# Gvove_-_Piezo_Vibration_Sensor_v1_1.net
KiCad netlist of a schematic drawn in EAGLE
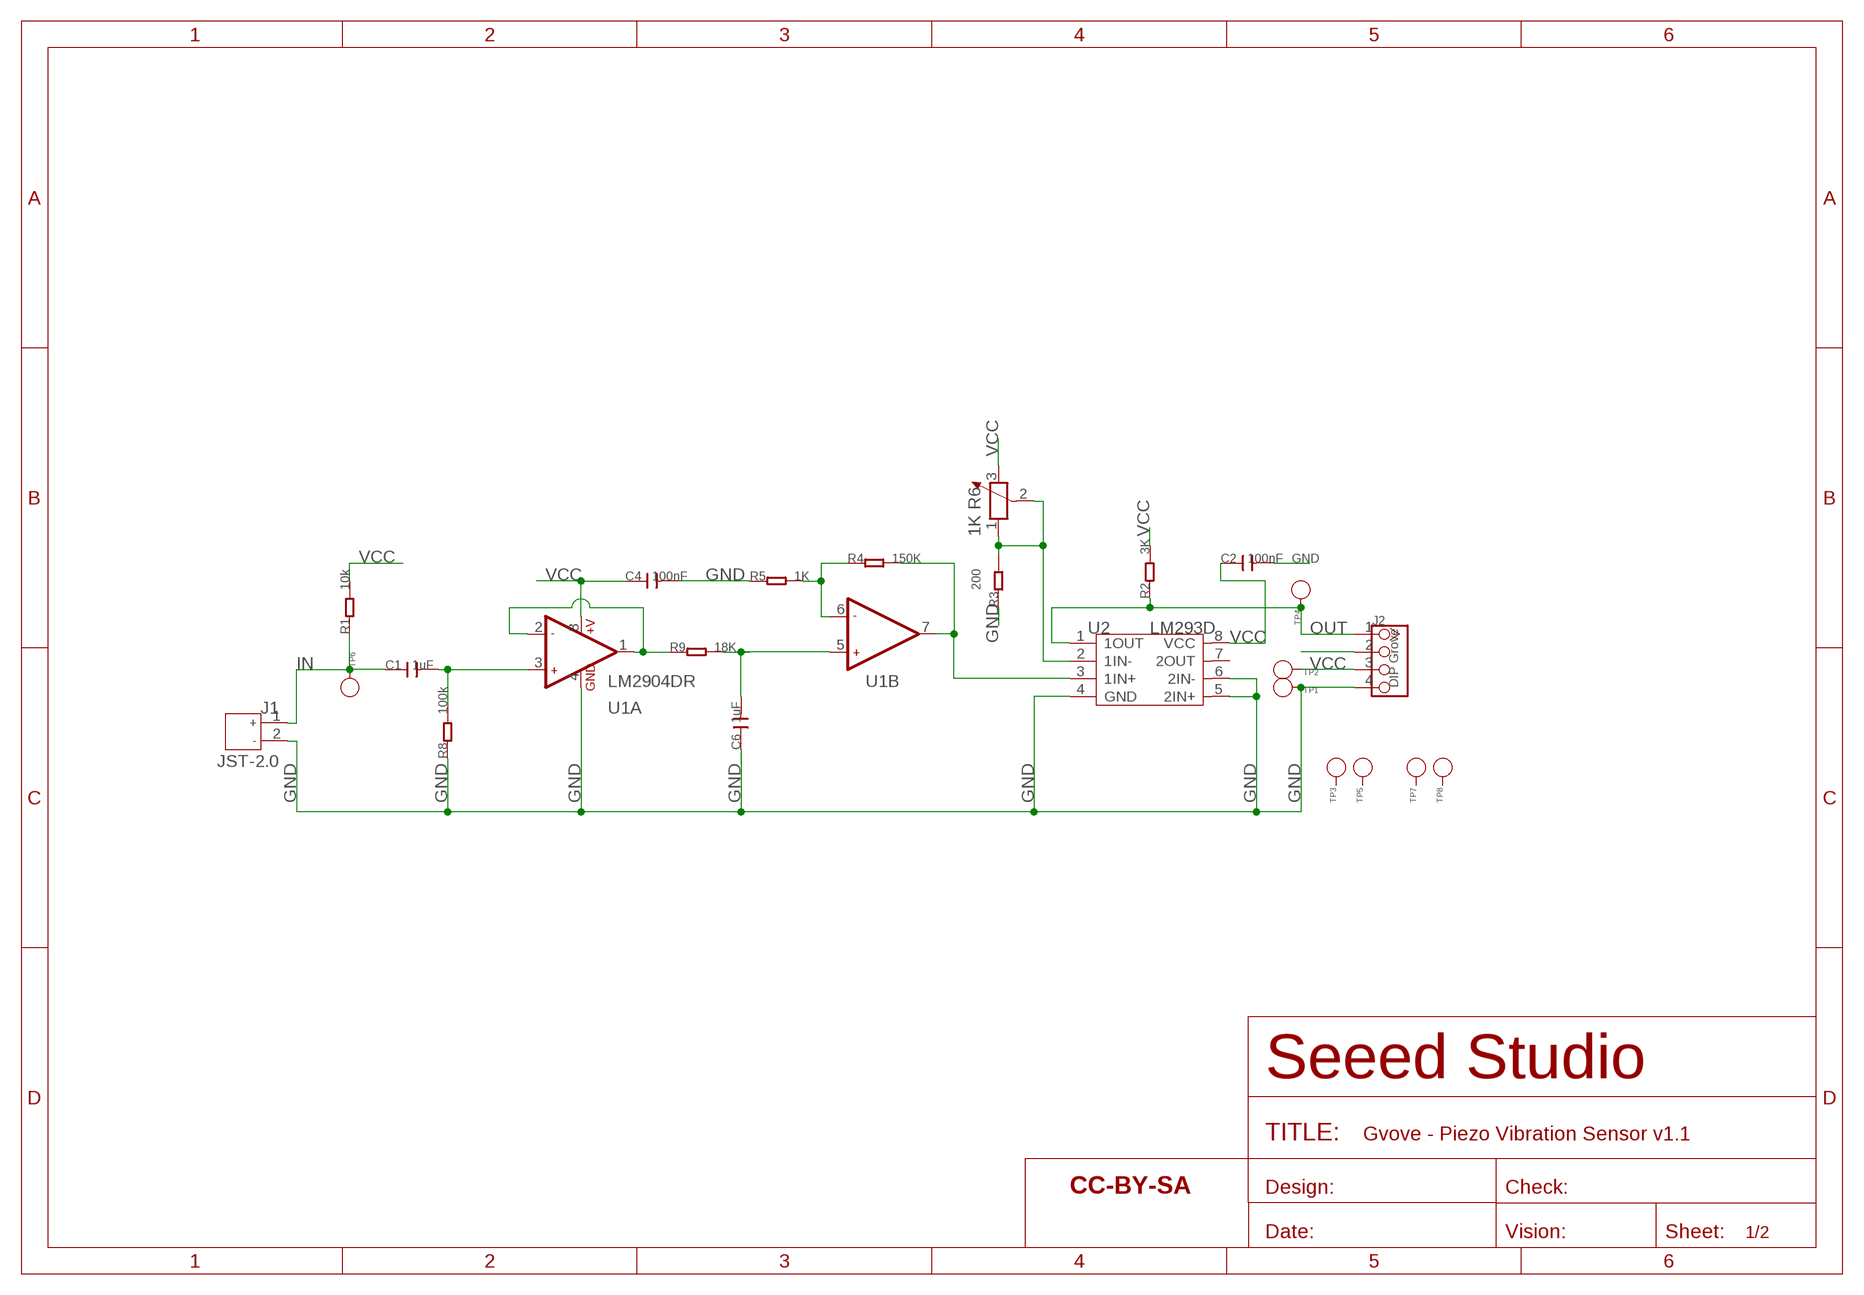
[diagram p0: schematic, sheet 1]
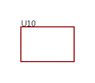
[diagram p1: schematic, sheet 2]

(export (version "E")
  (design (tool "Eeschema 10.0.6"))
  (components
    (comp (ref "U10")
      (value "TWIG'2U'")
      (footprint "eagle-import:GROVE-TEST-PLATFORM")
      (libsource (lib "eagle-import") (part "TWIG'2U'"))
    )
    (comp (ref "C1")
      (value "1uF")
      (footprint "eagle-import:C0603")
      (libsource (lib "eagle-import") (part "C-0603"))
    )
    (comp (ref "C2")
      (value "100nF")
      (footprint "eagle-import:C0603")
      (libsource (lib "eagle-import") (part "C-0603"))
    )
    (comp (ref "C4")
      (value "100nF")
      (footprint "eagle-import:C0603")
      (libsource (lib "eagle-import") (part "C-0603"))
    )
    (comp (ref "C6")
      (value "1uF")
      (footprint "eagle-import:C0603")
      (libsource (lib "eagle-import") (part "C-0603"))
    )
    (comp (ref "J1")
      (value "JST-2.0")
      (footprint "eagle-import:JST-2.0")
      (libsource (lib "eagle-import") (part "JACK-JST-2P-PW'2.0'"))
    )
    (comp (ref "J2")
      (value "DIP Grove")
      (footprint "eagle-import:4P-2.0")
      (libsource (lib "eagle-import") (part "TWIG-4P-2.0-2.0"))
    )
    (comp (ref "R1")
      (value "10k")
      (footprint "eagle-import:R0603")
      (libsource (lib "eagle-import") (part "R-0603"))
    )
    (comp (ref "R2")
      (value "3K")
      (footprint "eagle-import:R0603")
      (libsource (lib "eagle-import") (part "R-0603"))
    )
    (comp (ref "R3")
      (value "200")
      (footprint "eagle-import:R0603")
      (libsource (lib "eagle-import") (part "R-0603"))
    )
    (comp (ref "R4")
      (value "150K")
      (footprint "eagle-import:R0603")
      (libsource (lib "eagle-import") (part "R-0603"))
    )
    (comp (ref "R5")
      (value "1K")
      (footprint "eagle-import:R0603")
      (libsource (lib "eagle-import") (part "R-0603"))
    )
    (comp (ref "R6")
      (value "1K")
      (footprint "eagle-import:3P-SMD-SQUA-4.6X3.7")
      (libsource (lib "eagle-import") (part "R-POTENTIOMETER'RTRIM3214W'"))
    )
    (comp (ref "R8")
      (value "100k")
      (footprint "eagle-import:R0603")
      (libsource (lib "eagle-import") (part "R-0603"))
    )
    (comp (ref "R9")
      (value "18K")
      (footprint "eagle-import:R0603")
      (libsource (lib "eagle-import") (part "R-0603"))
    )
    (comp (ref "TP1")
      (value "PAD-TEST-POINT'4545'")
      (footprint "eagle-import:TP_4545")
      (fields (field (name "PARTNO") "DNP"))
      (libsource (lib "eagle-import") (part "PAD-TEST-POINT'4545'"))
    )
    (comp (ref "TP2")
      (value "PAD-TEST-POINT'4545'")
      (footprint "eagle-import:TP_4545")
      (fields (field (name "PARTNO") "DNP"))
      (libsource (lib "eagle-import") (part "PAD-TEST-POINT'4545'"))
    )
    (comp (ref "TP3")
      (value "PAD-TEST-POINT'4545'")
      (footprint "eagle-import:TP_4545")
      (fields (field (name "PARTNO") "DNP"))
      (libsource (lib "eagle-import") (part "PAD-TEST-POINT'4545'"))
    )
    (comp (ref "TP4")
      (value "PAD-TEST-POINT'4545'")
      (footprint "eagle-import:TP_4545")
      (fields (field (name "PARTNO") "DNP"))
      (libsource (lib "eagle-import") (part "PAD-TEST-POINT'4545'"))
    )
    (comp (ref "TP5")
      (value "PAD-TEST-POINT'4545'")
      (footprint "eagle-import:TP_4545")
      (fields (field (name "PARTNO") "DNP"))
      (libsource (lib "eagle-import") (part "PAD-TEST-POINT'4545'"))
    )
    (comp (ref "TP6")
      (value "PAD-TEST-POINT'4545'")
      (footprint "eagle-import:TP_4545")
      (fields (field (name "PARTNO") "DNP"))
      (libsource (lib "eagle-import") (part "PAD-TEST-POINT'4545'"))
    )
    (comp (ref "TP7")
      (value "PAD-TEST-POINT'4545'")
      (footprint "eagle-import:TP_4545")
      (fields (field (name "PARTNO") "DNP"))
      (libsource (lib "eagle-import") (part "PAD-TEST-POINT'4545'"))
    )
    (comp (ref "TP8")
      (value "PAD-TEST-POINT'4545'")
      (footprint "eagle-import:TP_4545")
      (fields (field (name "PARTNO") "DNP"))
      (libsource (lib "eagle-import") (part "PAD-TEST-POINT'4545'"))
    )
    (comp (ref "U$2")
      (value "SEEEDSTUDIO-OPEN-SCH-FRAME")
      (footprint "eagle-import:SEEEDSTUDIO-PCB-FRAME")
      (libsource (lib "eagle-import") (part "SEEEDSTUDIO-OPEN-SCH-FRAME"))
    )
    (comp (ref "U1")
      (value "LM2904DR")
      (footprint "eagle-import:SO08")
      (libsource (lib "eagle-import") (part "LMV358D"))
    )
    (comp (ref "U2")
      (value "LM293D")
      (footprint "eagle-import:SOIC8-6.0")
      (libsource (lib "eagle-import") (part "LM293D"))
    )
  )
  (nets
    (net (code "1") (name "GND") (class "Default")
      (node (ref "C2") (pin "2") (pinfunction "2_2") (pintype "passive"))
      (node (ref "C4") (pin "2") (pinfunction "2_2") (pintype "passive"))
      (node (ref "C6") (pin "1") (pinfunction "1_1") (pintype "passive"))
      (node (ref "J1") (pin "2") (pinfunction "P$2_2") (pintype "bidirectional"))
      (node (ref "J2") (pin "4") (pinfunction "4_4") (pintype "bidirectional"))
      (node (ref "R3") (pin "1") (pinfunction "1_1") (pintype "passive"))
      (node (ref "R5") (pin "1") (pinfunction "1_1") (pintype "passive"))
      (node (ref "R8") (pin "1") (pinfunction "1_1") (pintype "passive"))
      (node (ref "TP1") (pin "T") (pinfunction "T_T") (pintype "bidirectional"))
      (node (ref "U1") (pin "4") (pinfunction "GND_4") (pintype "power_in"))
      (node (ref "U2") (pin "4") (pinfunction "GND_4") (pintype "power_in"))
      (node (ref "U2") (pin "5") (pinfunction "2IN+_5") (pintype "input"))
      (node (ref "U2") (pin "6") (pinfunction "2IN-_6") (pintype "input"))
    )
    (net (code "2") (name "IN") (class "Default")
      (node (ref "C1") (pin "1") (pinfunction "1_1") (pintype "passive"))
      (node (ref "J1") (pin "1") (pinfunction "P$1_1") (pintype "bidirectional"))
      (node (ref "R1") (pin "1") (pinfunction "1_1") (pintype "passive"))
      (node (ref "TP6") (pin "T") (pinfunction "T_T") (pintype "bidirectional"))
    )
    (net (code "3") (name "Net-(R6-3)") (class "Default")
      (node (ref "R3") (pin "2") (pinfunction "2_2") (pintype "passive"))
      (node (ref "R6") (pin "1") (pinfunction "1_1") (pintype "passive"))
      (node (ref "R6") (pin "2") (pinfunction "3_2") (pintype "passive"))
      (node (ref "U2") (pin "2") (pinfunction "1IN-_2") (pintype "input"))
    )
    (net (code "4") (name "Net-(U1A-+IN1)") (class "Default")
      (node (ref "C1") (pin "2") (pinfunction "2_2") (pintype "passive"))
      (node (ref "R8") (pin "2") (pinfunction "2_2") (pintype "passive"))
      (node (ref "U1") (pin "3") (pinfunction "+IN1_3") (pintype "input"))
    )
    (net (code "5") (name "Net-(U1A--IN1)") (class "Default")
      (node (ref "R9") (pin "1") (pinfunction "1_1") (pintype "passive"))
      (node (ref "U1") (pin "1") (pinfunction "OUT1_1") (pintype "output"))
      (node (ref "U1") (pin "2") (pinfunction "-IN1_2") (pintype "input"))
    )
    (net (code "6") (name "Net-(U1B-+IN2)") (class "Default")
      (node (ref "C6") (pin "2") (pinfunction "2_2") (pintype "passive"))
      (node (ref "R9") (pin "2") (pinfunction "2_2") (pintype "passive"))
      (node (ref "U1") (pin "5") (pinfunction "+IN2_5") (pintype "input"))
    )
    (net (code "7") (name "Net-(U1B--IN2)") (class "Default")
      (node (ref "R4") (pin "1") (pinfunction "1_1") (pintype "passive"))
      (node (ref "R5") (pin "2") (pinfunction "2_2") (pintype "passive"))
      (node (ref "U1") (pin "6") (pinfunction "-IN2_6") (pintype "input"))
    )
    (net (code "8") (name "Net-(U1B-OUT2)") (class "Default")
      (node (ref "R4") (pin "2") (pinfunction "2_2") (pintype "passive"))
      (node (ref "U1") (pin "7") (pinfunction "OUT2_7") (pintype "output"))
      (node (ref "U2") (pin "3") (pinfunction "1IN+_3") (pintype "input"))
    )
    (net (code "9") (name "OUT") (class "Default")
      (node (ref "J2") (pin "1") (pinfunction "1_1") (pintype "bidirectional"))
      (node (ref "R2") (pin "1") (pinfunction "1_1") (pintype "passive"))
      (node (ref "TP4") (pin "T") (pinfunction "T_T") (pintype "bidirectional"))
      (node (ref "U2") (pin "1") (pinfunction "1OUT_1") (pintype "output"))
    )
    (net (code "10") (name "VCC") (class "Default")
      (node (ref "C2") (pin "1") (pinfunction "1_1") (pintype "passive"))
      (node (ref "C4") (pin "1") (pinfunction "1_1") (pintype "passive"))
      (node (ref "J2") (pin "3") (pinfunction "3_3") (pintype "bidirectional"))
      (node (ref "R1") (pin "2") (pinfunction "2_2") (pintype "passive"))
      (node (ref "R2") (pin "2") (pinfunction "2_2") (pintype "passive"))
      (node (ref "R6") (pin "3") (pinfunction "2_3") (pintype "passive"))
      (node (ref "TP2") (pin "T") (pinfunction "T_T") (pintype "bidirectional"))
      (node (ref "U1") (pin "8") (pinfunction "+V_8") (pintype "power_in"))
      (node (ref "U2") (pin "8") (pinfunction "VCC_8") (pintype "power_in"))
    )
    (net (code "11") (name "unconnected-(J2-Pad2)") (class "Default")
      (node (ref "J2") (pin "2") (pinfunction "2_2") (pintype "bidirectional"))
    )
    (net (code "12") (name "unconnected-(TP3-PadT)") (class "Default")
      (node (ref "TP3") (pin "T") (pinfunction "T_T") (pintype "bidirectional"))
    )
    (net (code "13") (name "unconnected-(TP5-PadT)") (class "Default")
      (node (ref "TP5") (pin "T") (pinfunction "T_T") (pintype "bidirectional"))
    )
    (net (code "14") (name "unconnected-(TP7-PadT)") (class "Default")
      (node (ref "TP7") (pin "T") (pinfunction "T_T") (pintype "bidirectional"))
    )
    (net (code "15") (name "unconnected-(TP8-PadT)") (class "Default")
      (node (ref "TP8") (pin "T") (pinfunction "T_T") (pintype "bidirectional"))
    )
    (net (code "16") (name "unconnected-(U2-2OUT-Pad7)") (class "Default")
      (node (ref "U2") (pin "7") (pinfunction "2OUT_7") (pintype "output"))
    )
  )
)
